# Sheet1.net
KiCad netlist of a schematic drawn in Altium Designer
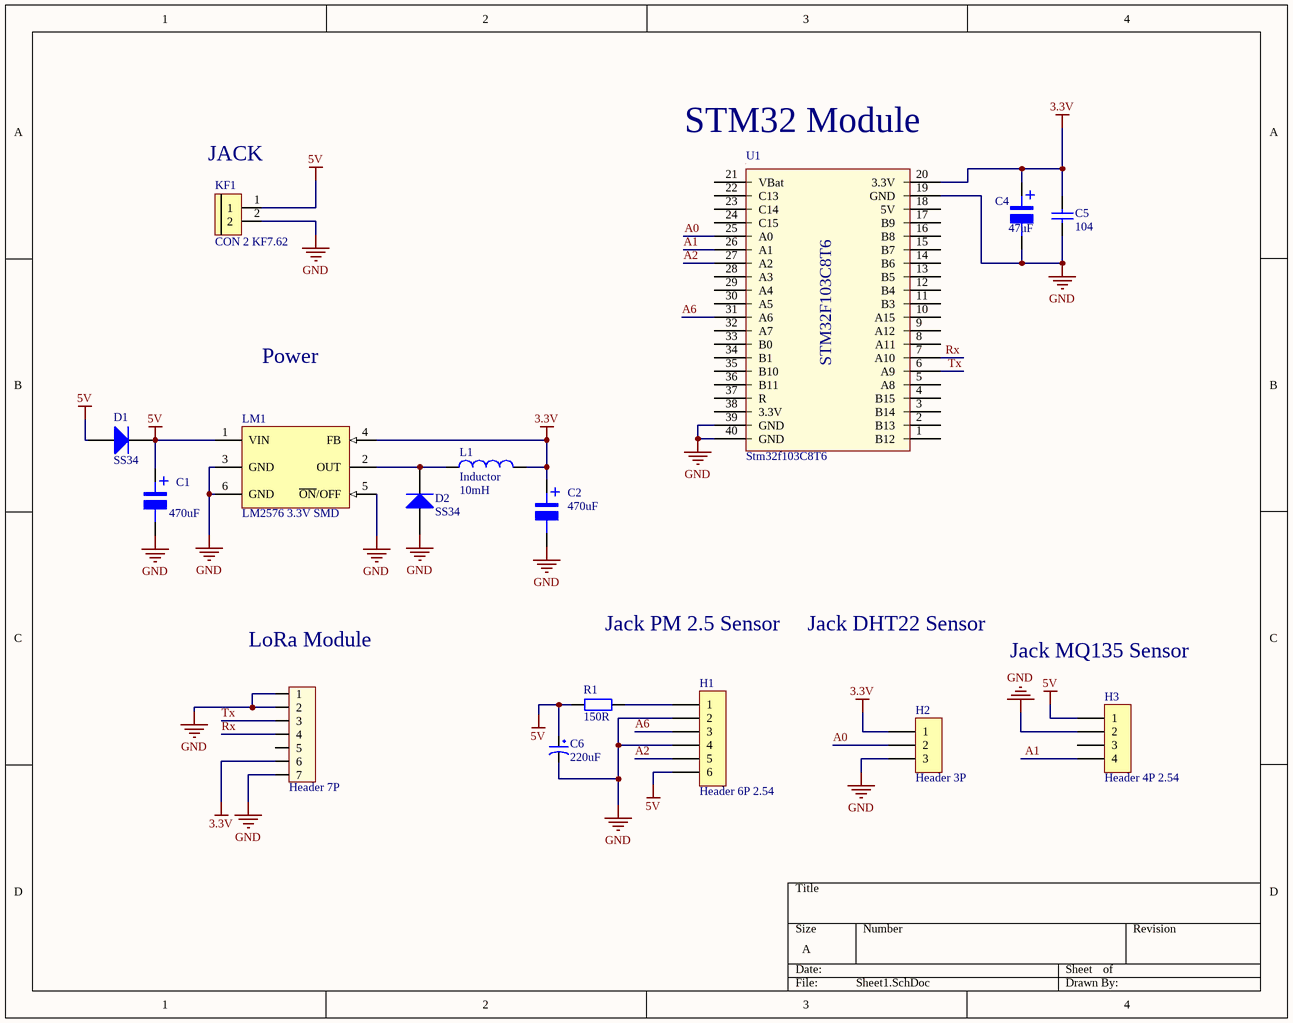
[diagram p0: Sheet1.SchDoc]

(export (version "E")
  (design (tool "Eeschema 10.0.6"))
  (components
    (comp (ref "C1")
      (value "470uF")
      (footprint "tu nhom 6.3 (d)")
      (description "Dán")
      (libsource (lib "Altium_Lib_by_KhueNguyenCreator") (part "Tu Nhom 47uF 25V"))
    )
    (comp (ref "C2")
      (value "470uF")
      (footprint "tu nhom 6.3 (d)")
      (description "Dán")
      (libsource (lib "Altium_Lib_by_KhueNguyenCreator") (part "Tu Nhom 47uF 25V"))
    )
    (comp (ref "C4")
      (value "47uF")
      (footprint "tu nhom 6.3 (d)")
      (description "Dán")
      (libsource (lib "Altium_Lib_by_KhueNguyenCreator") (part "Tu Nhom 47uF 25V"))
    )
    (comp (ref "C5")
      (value "104")
      (footprint "tu 0805")
      (description "Dán")
      (libsource (lib "Altium_Lib_by_KhueNguyenCreator") (part "Tu 0805 104 50V 10%"))
    )
    (comp (ref "C6")
      (value "220uF")
      (footprint "tu hoa 5mm")
      (description "Cắm")
      (libsource (lib "Altium_Lib_by_KhueNguyenCreator") (part "Tu Hoa 220uF 10V 6x11"))
    )
    (comp (ref "D1")
      (value "SS34")
      (footprint "DIODE SMA")
      (description "Dán")
      (libsource (lib "Altium_Lib_by_KhueNguyenCreator") (part "Diode SS34 ( 1N5822 )"))
    )
    (comp (ref "D2")
      (value "SS34")
      (footprint "DIODE SMA")
      (description "Dán")
      (libsource (lib "Altium_Lib_by_KhueNguyenCreator") (part "Diode SS34 ( 1N5822 )"))
    )
    (comp (ref "H1")
      (value "Header 6P 2.54")
      (footprint "Header 6P DC 2.54")
      (description "Cắm")
      (libsource (lib "Altium_Lib_by_KhueNguyenCreator") (part "Header 6P 2.54 Duc Cong"))
    )
    (comp (ref "H2")
      (value "Header 3P")
      (footprint "Header 3P DC 2.54")
      (description "Cắm")
      (libsource (lib "Altium_Lib_by_KhueNguyenCreator") (part "Header 3P 2.54 Duc Cong"))
    )
    (comp (ref "H3")
      (value "Header 4P 2.54")
      (footprint "Header 4P DC 2.54")
      (description "Cắm")
      (libsource (lib "Altium_Lib_by_KhueNguyenCreator") (part "Header 4P 2.54 Duc Cong"))
    )
    (comp (ref "H4")
      (value "Header 7P")
      (footprint "Header 7P DC 2.54")
      (description "Cắm")
      (libsource (lib "Altium_Lib_by_KhueNguyenCreator") (part "Header 7P 2.54 Duc Cong"))
    )
    (comp (ref "KF1")
      (value "CON 2 KF7.62")
      (footprint "CON 2 KF7.62")
      (description "Cắm")
      (libsource (lib "Altium_Lib_by_KhueNguyenCreator") (part "CON 2 KF7.62"))
    )
    (comp (ref "L1")
      (value "Inductor")
      (footprint "0402-A")
      (fields (field (name "ALTIUM_VALUE") "10mH") (field (name "PUBLISHER") "Altium Limited"))
      (libsource (lib "Miscellaneous Devices") (part "Inductor"))
    )
    (comp (ref "LM1")
      (value "LM2576 3.3V SMD")
      (footprint "TO263-5")
      (description "Dán")
      (libsource (lib "Altium_Lib_by_KhueNguyenCreator") (part "LM2576 3.3V SMD"))
    )
    (comp (ref "R1")
      (value "150R")
      (footprint "tro smd 0805")
      (description "Dán")
      (libsource (lib "Altium_Lib_by_KhueNguyenCreator") (part "Tro 0805 5% 150R"))
    )
    (comp (ref "U1")
      (value "Stm32f103C8T6")
      (footprint "PCBComponent_1")
      (libsource (lib "Stm32f103c8t6") (part "Stm32F103C8T6"))
    )
  )
  (nets
    (net (code "1") (name "/A0") (class "Default")
      (node (ref "H2") (pin "2") (pinfunction "2_2") (pintype "passive"))
      (node (ref "U1") (pin "25") (pinfunction "A0_25") (pintype "passive"))
    )
    (net (code "2") (name "/A1") (class "Default")
      (node (ref "H3") (pin "4") (pinfunction "4_4") (pintype "passive"))
      (node (ref "U1") (pin "26") (pinfunction "A1_26") (pintype "passive"))
    )
    (net (code "3") (name "/A2") (class "Default")
      (node (ref "H1") (pin "5") (pinfunction "5_5") (pintype "passive"))
      (node (ref "U1") (pin "27") (pinfunction "A2_27") (pintype "passive"))
    )
    (net (code "4") (name "/A6") (class "Default")
      (node (ref "H1") (pin "3") (pinfunction "3_3") (pintype "passive"))
      (node (ref "U1") (pin "31") (pinfunction "A6_31") (pintype "passive"))
    )
    (net (code "5") (name "/Rx") (class "Default")
      (node (ref "H4") (pin "4") (pinfunction "4_4") (pintype "passive"))
      (node (ref "U1") (pin "7") (pinfunction "A10_7") (pintype "passive"))
    )
    (net (code "6") (name "/Tx") (class "Default")
      (node (ref "H4") (pin "3") (pinfunction "3_3") (pintype "passive"))
      (node (ref "U1") (pin "6") (pinfunction "A9_6") (pintype "passive"))
    )
    (net (code "7") (name "3.3V") (class "Default")
      (node (ref "C2") (pin "1") (pinfunction "1_1") (pintype "passive"))
      (node (ref "C4") (pin "1") (pinfunction "1_1") (pintype "passive"))
      (node (ref "C5") (pin "2") (pinfunction "2_2") (pintype "passive"))
      (node (ref "H2") (pin "1") (pinfunction "1_1") (pintype "passive"))
      (node (ref "H4") (pin "6") (pinfunction "6_6") (pintype "passive"))
      (node (ref "L1") (pin "2") (pinfunction "2_2") (pintype "passive"))
      (node (ref "LM1") (pin "4") (pinfunction "FB_4") (pintype "input"))
      (node (ref "U1") (pin "20") (pinfunction "3.3V_20") (pintype "passive"))
    )
    (net (code "8") (name "5V") (class "Default")
      (node (ref "C1") (pin "1") (pinfunction "1_1") (pintype "passive"))
      (node (ref "C6") (pin "1") (pinfunction "1_1") (pintype "passive"))
      (node (ref "D1") (pin "1") (pinfunction "A_1") (pintype "passive"))
      (node (ref "D1") (pin "2") (pinfunction "K_2") (pintype "passive"))
      (node (ref "H1") (pin "6") (pinfunction "6_6") (pintype "passive"))
      (node (ref "H3") (pin "1") (pinfunction "1_1") (pintype "passive"))
      (node (ref "KF1") (pin "1") (pinfunction "1_1") (pintype "passive"))
      (node (ref "LM1") (pin "1") (pinfunction "VIN_1") (pintype "power_in"))
      (node (ref "R1") (pin "1") (pinfunction "1_1") (pintype "passive"))
    )
    (net (code "9") (name "GND") (class "Default")
      (node (ref "C1") (pin "2") (pinfunction "2_2") (pintype "passive"))
      (node (ref "C2") (pin "2") (pinfunction "2_2") (pintype "passive"))
      (node (ref "C4") (pin "2") (pinfunction "2_2") (pintype "passive"))
      (node (ref "C5") (pin "1") (pinfunction "1_1") (pintype "passive"))
      (node (ref "C6") (pin "2") (pinfunction "2_2") (pintype "passive"))
      (node (ref "D2") (pin "1") (pinfunction "A_1") (pintype "passive"))
      (node (ref "H1") (pin "2") (pinfunction "2_2") (pintype "passive"))
      (node (ref "H1") (pin "4") (pinfunction "4_4") (pintype "passive"))
      (node (ref "H2") (pin "3") (pinfunction "3_3") (pintype "passive"))
      (node (ref "H3") (pin "2") (pinfunction "2_2") (pintype "passive"))
      (node (ref "H4") (pin "1") (pinfunction "1_1") (pintype "passive"))
      (node (ref "H4") (pin "2") (pinfunction "2_2") (pintype "passive"))
      (node (ref "H4") (pin "7") (pinfunction "7_7") (pintype "passive"))
      (node (ref "KF1") (pin "2") (pinfunction "2_2") (pintype "passive"))
      (node (ref "LM1") (pin "3") (pinfunction "GND_3") (pintype "power_in"))
      (node (ref "LM1") (pin "5") (pinfunction "~{ON}/OFF_5") (pintype "input"))
      (node (ref "LM1") (pin "6") (pinfunction "GND_6") (pintype "passive"))
      (node (ref "U1") (pin "19") (pinfunction "GND_19") (pintype "passive"))
      (node (ref "U1") (pin "39") (pinfunction "GND_39") (pintype "passive"))
      (node (ref "U1") (pin "40") (pinfunction "GND_40") (pintype "passive"))
    )
    (net (code "10") (name "Net-(D2-K)") (class "Default")
      (node (ref "D2") (pin "2") (pinfunction "K_2") (pintype "passive"))
      (node (ref "L1") (pin "1") (pinfunction "1_1") (pintype "passive"))
      (node (ref "LM1") (pin "2") (pinfunction "OUT_2") (pintype "power_in"))
    )
    (net (code "11") (name "Net-(H1-Pad1)") (class "Default")
      (node (ref "H1") (pin "1") (pinfunction "1_1") (pintype "passive"))
      (node (ref "R1") (pin "2") (pinfunction "2_2") (pintype "passive"))
    )
    (net (code "12") (name "unconnected-(H3-Pad3)") (class "Default")
      (node (ref "H3") (pin "3") (pinfunction "3_3") (pintype "passive"))
    )
    (net (code "13") (name "unconnected-(H4-Pad5)") (class "Default")
      (node (ref "H4") (pin "5") (pinfunction "5_5") (pintype "passive"))
    )
    (net (code "14") (name "unconnected-(U1-3.3V-Pad38)") (class "Default")
      (node (ref "U1") (pin "38") (pinfunction "3.3V_38") (pintype "passive"))
    )
    (net (code "15") (name "unconnected-(U1-5V-Pad18)") (class "Default")
      (node (ref "U1") (pin "18") (pinfunction "5V_18") (pintype "passive"))
    )
    (net (code "16") (name "unconnected-(U1-A3-Pad28)") (class "Default")
      (node (ref "U1") (pin "28") (pinfunction "A3_28") (pintype "passive"))
    )
    (net (code "17") (name "unconnected-(U1-A4-Pad29)") (class "Default")
      (node (ref "U1") (pin "29") (pinfunction "A4_29") (pintype "passive"))
    )
    (net (code "18") (name "unconnected-(U1-A5-Pad30)") (class "Default")
      (node (ref "U1") (pin "30") (pinfunction "A5_30") (pintype "passive"))
    )
    (net (code "19") (name "unconnected-(U1-A7-Pad32)") (class "Default")
      (node (ref "U1") (pin "32") (pinfunction "A7_32") (pintype "passive"))
    )
    (net (code "20") (name "unconnected-(U1-A8-Pad5)") (class "Default")
      (node (ref "U1") (pin "5") (pinfunction "A8_5") (pintype "passive"))
    )
    (net (code "21") (name "unconnected-(U1-A11-Pad8)") (class "Default")
      (node (ref "U1") (pin "8") (pinfunction "A11_8") (pintype "passive"))
    )
    (net (code "22") (name "unconnected-(U1-A12-Pad9)") (class "Default")
      (node (ref "U1") (pin "9") (pinfunction "A12_9") (pintype "passive"))
    )
    (net (code "23") (name "unconnected-(U1-A15-Pad10)") (class "Default")
      (node (ref "U1") (pin "10") (pinfunction "A15_10") (pintype "passive"))
    )
    (net (code "24") (name "unconnected-(U1-B0-Pad33)") (class "Default")
      (node (ref "U1") (pin "33") (pinfunction "B0_33") (pintype "passive"))
    )
    (net (code "25") (name "unconnected-(U1-B1-Pad34)") (class "Default")
      (node (ref "U1") (pin "34") (pinfunction "B1_34") (pintype "passive"))
    )
    (net (code "26") (name "unconnected-(U1-B3-Pad11)") (class "Default")
      (node (ref "U1") (pin "11") (pinfunction "B3_11") (pintype "passive"))
    )
    (net (code "27") (name "unconnected-(U1-B4-Pad12)") (class "Default")
      (node (ref "U1") (pin "12") (pinfunction "B4_12") (pintype "passive"))
    )
    (net (code "28") (name "unconnected-(U1-B5-Pad13)") (class "Default")
      (node (ref "U1") (pin "13") (pinfunction "B5_13") (pintype "passive"))
    )
    (net (code "29") (name "unconnected-(U1-B6-Pad14)") (class "Default")
      (node (ref "U1") (pin "14") (pinfunction "B6_14") (pintype "passive"))
    )
    (net (code "30") (name "unconnected-(U1-B7-Pad15)") (class "Default")
      (node (ref "U1") (pin "15") (pinfunction "B7_15") (pintype "passive"))
    )
    (net (code "31") (name "unconnected-(U1-B8-Pad16)") (class "Default")
      (node (ref "U1") (pin "16") (pinfunction "B8_16") (pintype "passive"))
    )
    (net (code "32") (name "unconnected-(U1-B9-Pad17)") (class "Default")
      (node (ref "U1") (pin "17") (pinfunction "B9_17") (pintype "passive"))
    )
    (net (code "33") (name "unconnected-(U1-B10-Pad35)") (class "Default")
      (node (ref "U1") (pin "35") (pinfunction "B10_35") (pintype "passive"))
    )
    (net (code "34") (name "unconnected-(U1-B11-Pad36)") (class "Default")
      (node (ref "U1") (pin "36") (pinfunction "B11_36") (pintype "passive"))
    )
    (net (code "35") (name "unconnected-(U1-B12-Pad1)") (class "Default")
      (node (ref "U1") (pin "1") (pinfunction "B12_1") (pintype "passive"))
    )
    (net (code "36") (name "unconnected-(U1-B13-Pad2)") (class "Default")
      (node (ref "U1") (pin "2") (pinfunction "B13_2") (pintype "passive"))
    )
    (net (code "37") (name "unconnected-(U1-B14-Pad3)") (class "Default")
      (node (ref "U1") (pin "3") (pinfunction "B14_3") (pintype "passive"))
    )
    (net (code "38") (name "unconnected-(U1-B15-Pad4)") (class "Default")
      (node (ref "U1") (pin "4") (pinfunction "B15_4") (pintype "passive"))
    )
    (net (code "39") (name "unconnected-(U1-C13-Pad22)") (class "Default")
      (node (ref "U1") (pin "22") (pinfunction "C13_22") (pintype "passive"))
    )
    (net (code "40") (name "unconnected-(U1-C14-Pad23)") (class "Default")
      (node (ref "U1") (pin "23") (pinfunction "C14_23") (pintype "passive"))
    )
    (net (code "41") (name "unconnected-(U1-C15-Pad24)") (class "Default")
      (node (ref "U1") (pin "24") (pinfunction "C15_24") (pintype "passive"))
    )
    (net (code "42") (name "unconnected-(U1-R-Pad37)") (class "Default")
      (node (ref "U1") (pin "37") (pinfunction "R_37") (pintype "passive"))
    )
    (net (code "43") (name "unconnected-(U1-VBat-Pad21)") (class "Default")
      (node (ref "U1") (pin "21") (pinfunction "VBat_21") (pintype "passive"))
    )
  )
)
